# Radio_UFOP_revA.net
KiCad netlist of a schematic drawn in EAGLE
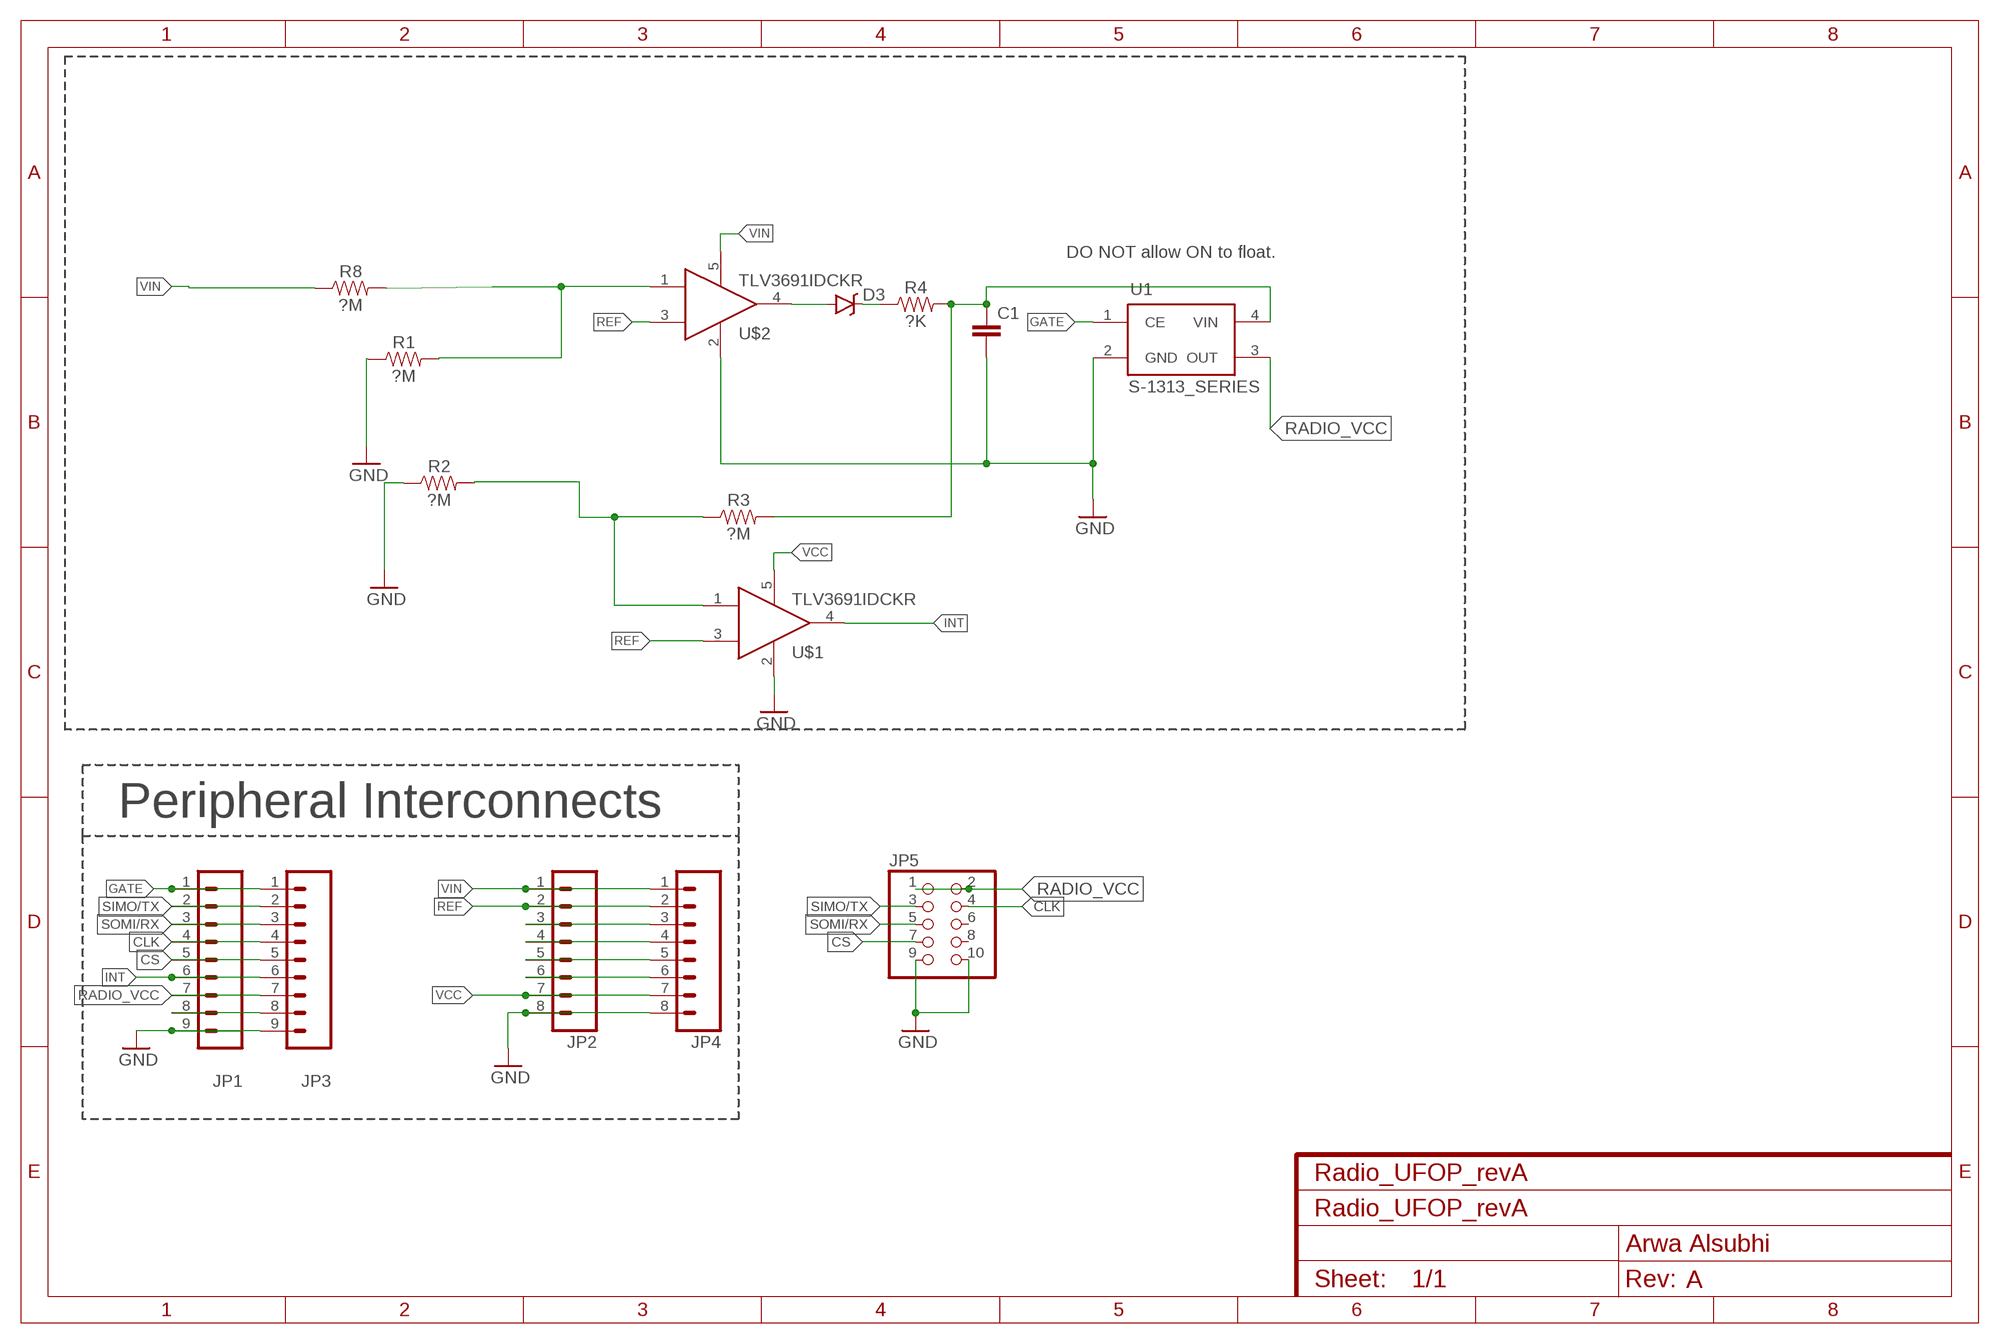
[diagram p0: schematic, sheet 1]

(export (version "E")
  (design (tool "Eeschema 10.0.6"))
  (components
    (comp (ref "C1")
      (value "CAP0603-CAP")
      (footprint "eagle-import:0603-CAP")
      (libsource (lib "eagle-import") (part "CAP0603-CAP"))
    )
    (comp (ref "D3")
      (value "RB751")
      (footprint "eagle-import:SOD-523")
      (fields (field (name "MPN") "BAS40-02V-V-G-08"))
      (libsource (lib "eagle-import") (part "DIODE-SCHOTTKY-RB751"))
    )
    (comp (ref "JP1")
      (value "M091.27MM")
      (footprint "eagle-import:1X09-1.27MM")
      (fields (field (name "MANUFACTURERPARTNUMBER") "GRPB091VWVN-RC ") (field (name "MPN") "GRPB091VWVN-RC"))
      (libsource (lib "eagle-import") (part "M091.27MM"))
    )
    (comp (ref "JP2")
      (value "M081.27MM")
      (footprint "eagle-import:1X08-1.27MM")
      (fields (field (name "MANUFACTURERPARTNUMBER") "GRPB081VWVN-RC "))
      (libsource (lib "eagle-import") (part "M081.27MM"))
    )
    (comp (ref "JP3")
      (value "M091.27MM")
      (footprint "eagle-import:1X09-1.27MM")
      (fields (field (name "MANUFACTURERPARTNUMBER") "GRPB091VWVN-RC ") (field (name "MPN") "GRPB091VWVN-RC"))
      (libsource (lib "eagle-import") (part "M091.27MM"))
    )
    (comp (ref "JP4")
      (value "M081.27MM")
      (footprint "eagle-import:1X08-1.27MM")
      (fields (field (name "MANUFACTURERPARTNUMBER") "GRPB081VWVN-RC "))
      (libsource (lib "eagle-import") (part "M081.27MM"))
    )
    (comp (ref "JP5")
      (value "PINHD-2X5")
      (footprint "eagle-import:2X05")
      (libsource (lib "eagle-import") (part "PINHD-2X5"))
    )
    (comp (ref "R1")
      (value "?M")
      (footprint "eagle-import:0805")
      (libsource (lib "eagle-import") (part "0.3OHM-0805-1/8W-1%"))
    )
    (comp (ref "R2")
      (value "?M")
      (footprint "eagle-import:0805")
      (libsource (lib "eagle-import") (part "0.3OHM-0805-1/8W-1%"))
    )
    (comp (ref "R3")
      (value "?M")
      (footprint "eagle-import:0805")
      (libsource (lib "eagle-import") (part "0.3OHM-0805-1/8W-1%"))
    )
    (comp (ref "R4")
      (value "?K")
      (footprint "eagle-import:0805")
      (libsource (lib "eagle-import") (part "0.3OHM-0805-1/8W-1%"))
    )
    (comp (ref "R8")
      (value "?M")
      (footprint "eagle-import:0805")
      (libsource (lib "eagle-import") (part "0.3OHM-0805-1/8W-1%"))
    )
    (comp (ref "U$1")
      (value "TLV3691IDCKR")
      (footprint "eagle-import:SOT353")
      (libsource (lib "eagle-import") (part "TLV3691IDCKR"))
    )
    (comp (ref "U$2")
      (value "TLV3691IDCKR")
      (footprint "eagle-import:SOT353")
      (libsource (lib "eagle-import") (part "TLV3691IDCKR"))
    )
    (comp (ref "U1")
      (value "S-1313_SERIES")
      (footprint "eagle-import:SC82-AB_1PRIMARY")
      (libsource (lib "eagle-import") (part "S-1313_SERIES"))
    )
  )
  (nets
    (net (code "1") (name "CLK") (class "Default")
      (node (ref "JP1") (pin "4") (pinfunction "4_4") (pintype "passive"))
      (node (ref "JP3") (pin "4") (pinfunction "4_4") (pintype "passive"))
      (node (ref "JP5") (pin "4") (pinfunction "4_4") (pintype "passive"))
    )
    (net (code "2") (name "CS") (class "Default")
      (node (ref "JP1") (pin "5") (pinfunction "5_5") (pintype "passive"))
      (node (ref "JP3") (pin "5") (pinfunction "5_5") (pintype "passive"))
      (node (ref "JP5") (pin "7") (pinfunction "7_7") (pintype "passive"))
    )
    (net (code "3") (name "GATE") (class "Default")
      (node (ref "JP1") (pin "1") (pinfunction "1_1") (pintype "passive"))
      (node (ref "JP3") (pin "1") (pinfunction "1_1") (pintype "passive"))
      (node (ref "U1") (pin "1") (pinfunction "CE_1") (pintype "bidirectional"))
    )
    (net (code "4") (name "GND") (class "Default")
      (node (ref "C1") (pin "2") (pinfunction "2_2") (pintype "passive"))
      (node (ref "JP1") (pin "9") (pinfunction "9_9") (pintype "passive"))
      (node (ref "JP2") (pin "8") (pinfunction "8_8") (pintype "passive"))
      (node (ref "JP3") (pin "9") (pinfunction "9_9") (pintype "passive"))
      (node (ref "JP4") (pin "8") (pinfunction "8_8") (pintype "passive"))
      (node (ref "JP5") (pin "10") (pinfunction "10_10") (pintype "passive"))
      (node (ref "JP5") (pin "9") (pinfunction "9_9") (pintype "passive"))
      (node (ref "R1") (pin "1") (pinfunction "1_1") (pintype "passive"))
      (node (ref "R2") (pin "1") (pinfunction "1_1") (pintype "passive"))
      (node (ref "U$1") (pin "2") (pinfunction "2_2") (pintype "bidirectional"))
      (node (ref "U$2") (pin "2") (pinfunction "2_2") (pintype "bidirectional"))
      (node (ref "U1") (pin "2") (pinfunction "GND_2") (pintype "bidirectional"))
    )
    (net (code "5") (name "INT") (class "Default")
      (node (ref "JP1") (pin "6") (pinfunction "6_6") (pintype "passive"))
      (node (ref "JP3") (pin "6") (pinfunction "6_6") (pintype "passive"))
      (node (ref "U$1") (pin "4") (pinfunction "4_4") (pintype "bidirectional"))
    )
    (net (code "6") (name "Net-(D3-PadA)") (class "Default")
      (node (ref "D3") (pin "A") (pinfunction "A_A") (pintype "passive"))
      (node (ref "U$2") (pin "4") (pinfunction "4_4") (pintype "bidirectional"))
    )
    (net (code "7") (name "Net-(D3-PadC)") (class "Default")
      (node (ref "D3") (pin "C") (pinfunction "C_C") (pintype "passive"))
      (node (ref "R4") (pin "1") (pinfunction "1_1") (pintype "passive"))
    )
    (net (code "8") (name "Net-(JP1-Pad8)") (class "Default")
      (node (ref "JP1") (pin "8") (pinfunction "8_8") (pintype "passive"))
      (node (ref "JP3") (pin "8") (pinfunction "8_8") (pintype "passive"))
    )
    (net (code "9") (name "Net-(JP2-Pad3)") (class "Default")
      (node (ref "JP2") (pin "3") (pinfunction "3_3") (pintype "passive"))
      (node (ref "JP4") (pin "3") (pinfunction "3_3") (pintype "passive"))
    )
    (net (code "10") (name "Net-(JP2-Pad4)") (class "Default")
      (node (ref "JP2") (pin "4") (pinfunction "4_4") (pintype "passive"))
      (node (ref "JP4") (pin "4") (pinfunction "4_4") (pintype "passive"))
    )
    (net (code "11") (name "Net-(JP2-Pad5)") (class "Default")
      (node (ref "JP2") (pin "5") (pinfunction "5_5") (pintype "passive"))
      (node (ref "JP4") (pin "5") (pinfunction "5_5") (pintype "passive"))
    )
    (net (code "12") (name "Net-(JP2-Pad6)") (class "Default")
      (node (ref "JP2") (pin "6") (pinfunction "6_6") (pintype "passive"))
      (node (ref "JP4") (pin "6") (pinfunction "6_6") (pintype "passive"))
    )
    (net (code "13") (name "Net-(R1-Pad2)") (class "Default")
      (node (ref "R1") (pin "2") (pinfunction "2_2") (pintype "passive"))
      (node (ref "R8") (pin "2") (pinfunction "2_2") (pintype "passive"))
      (node (ref "U$2") (pin "1") (pinfunction "1_1") (pintype "bidirectional"))
    )
    (net (code "14") (name "Net-(R2-Pad2)") (class "Default")
      (node (ref "R2") (pin "2") (pinfunction "2_2") (pintype "passive"))
      (node (ref "R3") (pin "1") (pinfunction "1_1") (pintype "passive"))
      (node (ref "U$1") (pin "1") (pinfunction "1_1") (pintype "bidirectional"))
    )
    (net (code "15") (name "Net-(U1-VIN)") (class "Default")
      (node (ref "C1") (pin "1") (pinfunction "1_1") (pintype "passive"))
      (node (ref "R3") (pin "2") (pinfunction "2_2") (pintype "passive"))
      (node (ref "R4") (pin "2") (pinfunction "2_2") (pintype "passive"))
      (node (ref "U1") (pin "4") (pinfunction "VIN_4") (pintype "bidirectional"))
    )
    (net (code "16") (name "RADIO_VCC") (class "Default")
      (node (ref "JP1") (pin "7") (pinfunction "7_7") (pintype "passive"))
      (node (ref "JP3") (pin "7") (pinfunction "7_7") (pintype "passive"))
      (node (ref "JP5") (pin "1") (pinfunction "1_1") (pintype "passive"))
      (node (ref "JP5") (pin "2") (pinfunction "2_2") (pintype "passive"))
      (node (ref "U1") (pin "3") (pinfunction "OUT_3") (pintype "bidirectional"))
    )
    (net (code "17") (name "REF") (class "Default")
      (node (ref "JP2") (pin "2") (pinfunction "2_2") (pintype "passive"))
      (node (ref "JP4") (pin "2") (pinfunction "2_2") (pintype "passive"))
      (node (ref "U$1") (pin "3") (pinfunction "3_3") (pintype "bidirectional"))
      (node (ref "U$2") (pin "3") (pinfunction "3_3") (pintype "bidirectional"))
    )
    (net (code "18") (name "SIMO{slash}TX") (class "Default")
      (node (ref "JP1") (pin "2") (pinfunction "2_2") (pintype "passive"))
      (node (ref "JP3") (pin "2") (pinfunction "2_2") (pintype "passive"))
      (node (ref "JP5") (pin "3") (pinfunction "3_3") (pintype "passive"))
    )
    (net (code "19") (name "SOMI{slash}RX") (class "Default")
      (node (ref "JP1") (pin "3") (pinfunction "3_3") (pintype "passive"))
      (node (ref "JP3") (pin "3") (pinfunction "3_3") (pintype "passive"))
      (node (ref "JP5") (pin "5") (pinfunction "5_5") (pintype "passive"))
    )
    (net (code "20") (name "VCC") (class "Default")
      (node (ref "JP2") (pin "7") (pinfunction "7_7") (pintype "passive"))
      (node (ref "JP4") (pin "7") (pinfunction "7_7") (pintype "passive"))
      (node (ref "U$1") (pin "5") (pinfunction "5_5") (pintype "bidirectional"))
    )
    (net (code "21") (name "VIN") (class "Default")
      (node (ref "JP2") (pin "1") (pinfunction "1_1") (pintype "passive"))
      (node (ref "JP4") (pin "1") (pinfunction "1_1") (pintype "passive"))
      (node (ref "R8") (pin "1") (pinfunction "1_1") (pintype "passive"))
      (node (ref "U$2") (pin "5") (pinfunction "5_5") (pintype "bidirectional"))
    )
    (net (code "22") (name "unconnected-(JP5-Pad6)") (class "Default")
      (node (ref "JP5") (pin "6") (pinfunction "6_6") (pintype "passive"))
    )
    (net (code "23") (name "unconnected-(JP5-Pad8)") (class "Default")
      (node (ref "JP5") (pin "8") (pinfunction "8_8") (pintype "passive"))
    )
  )
)
